# ProjectSIT210.net
KiCad netlist of a schematic drawn in EasyEDA
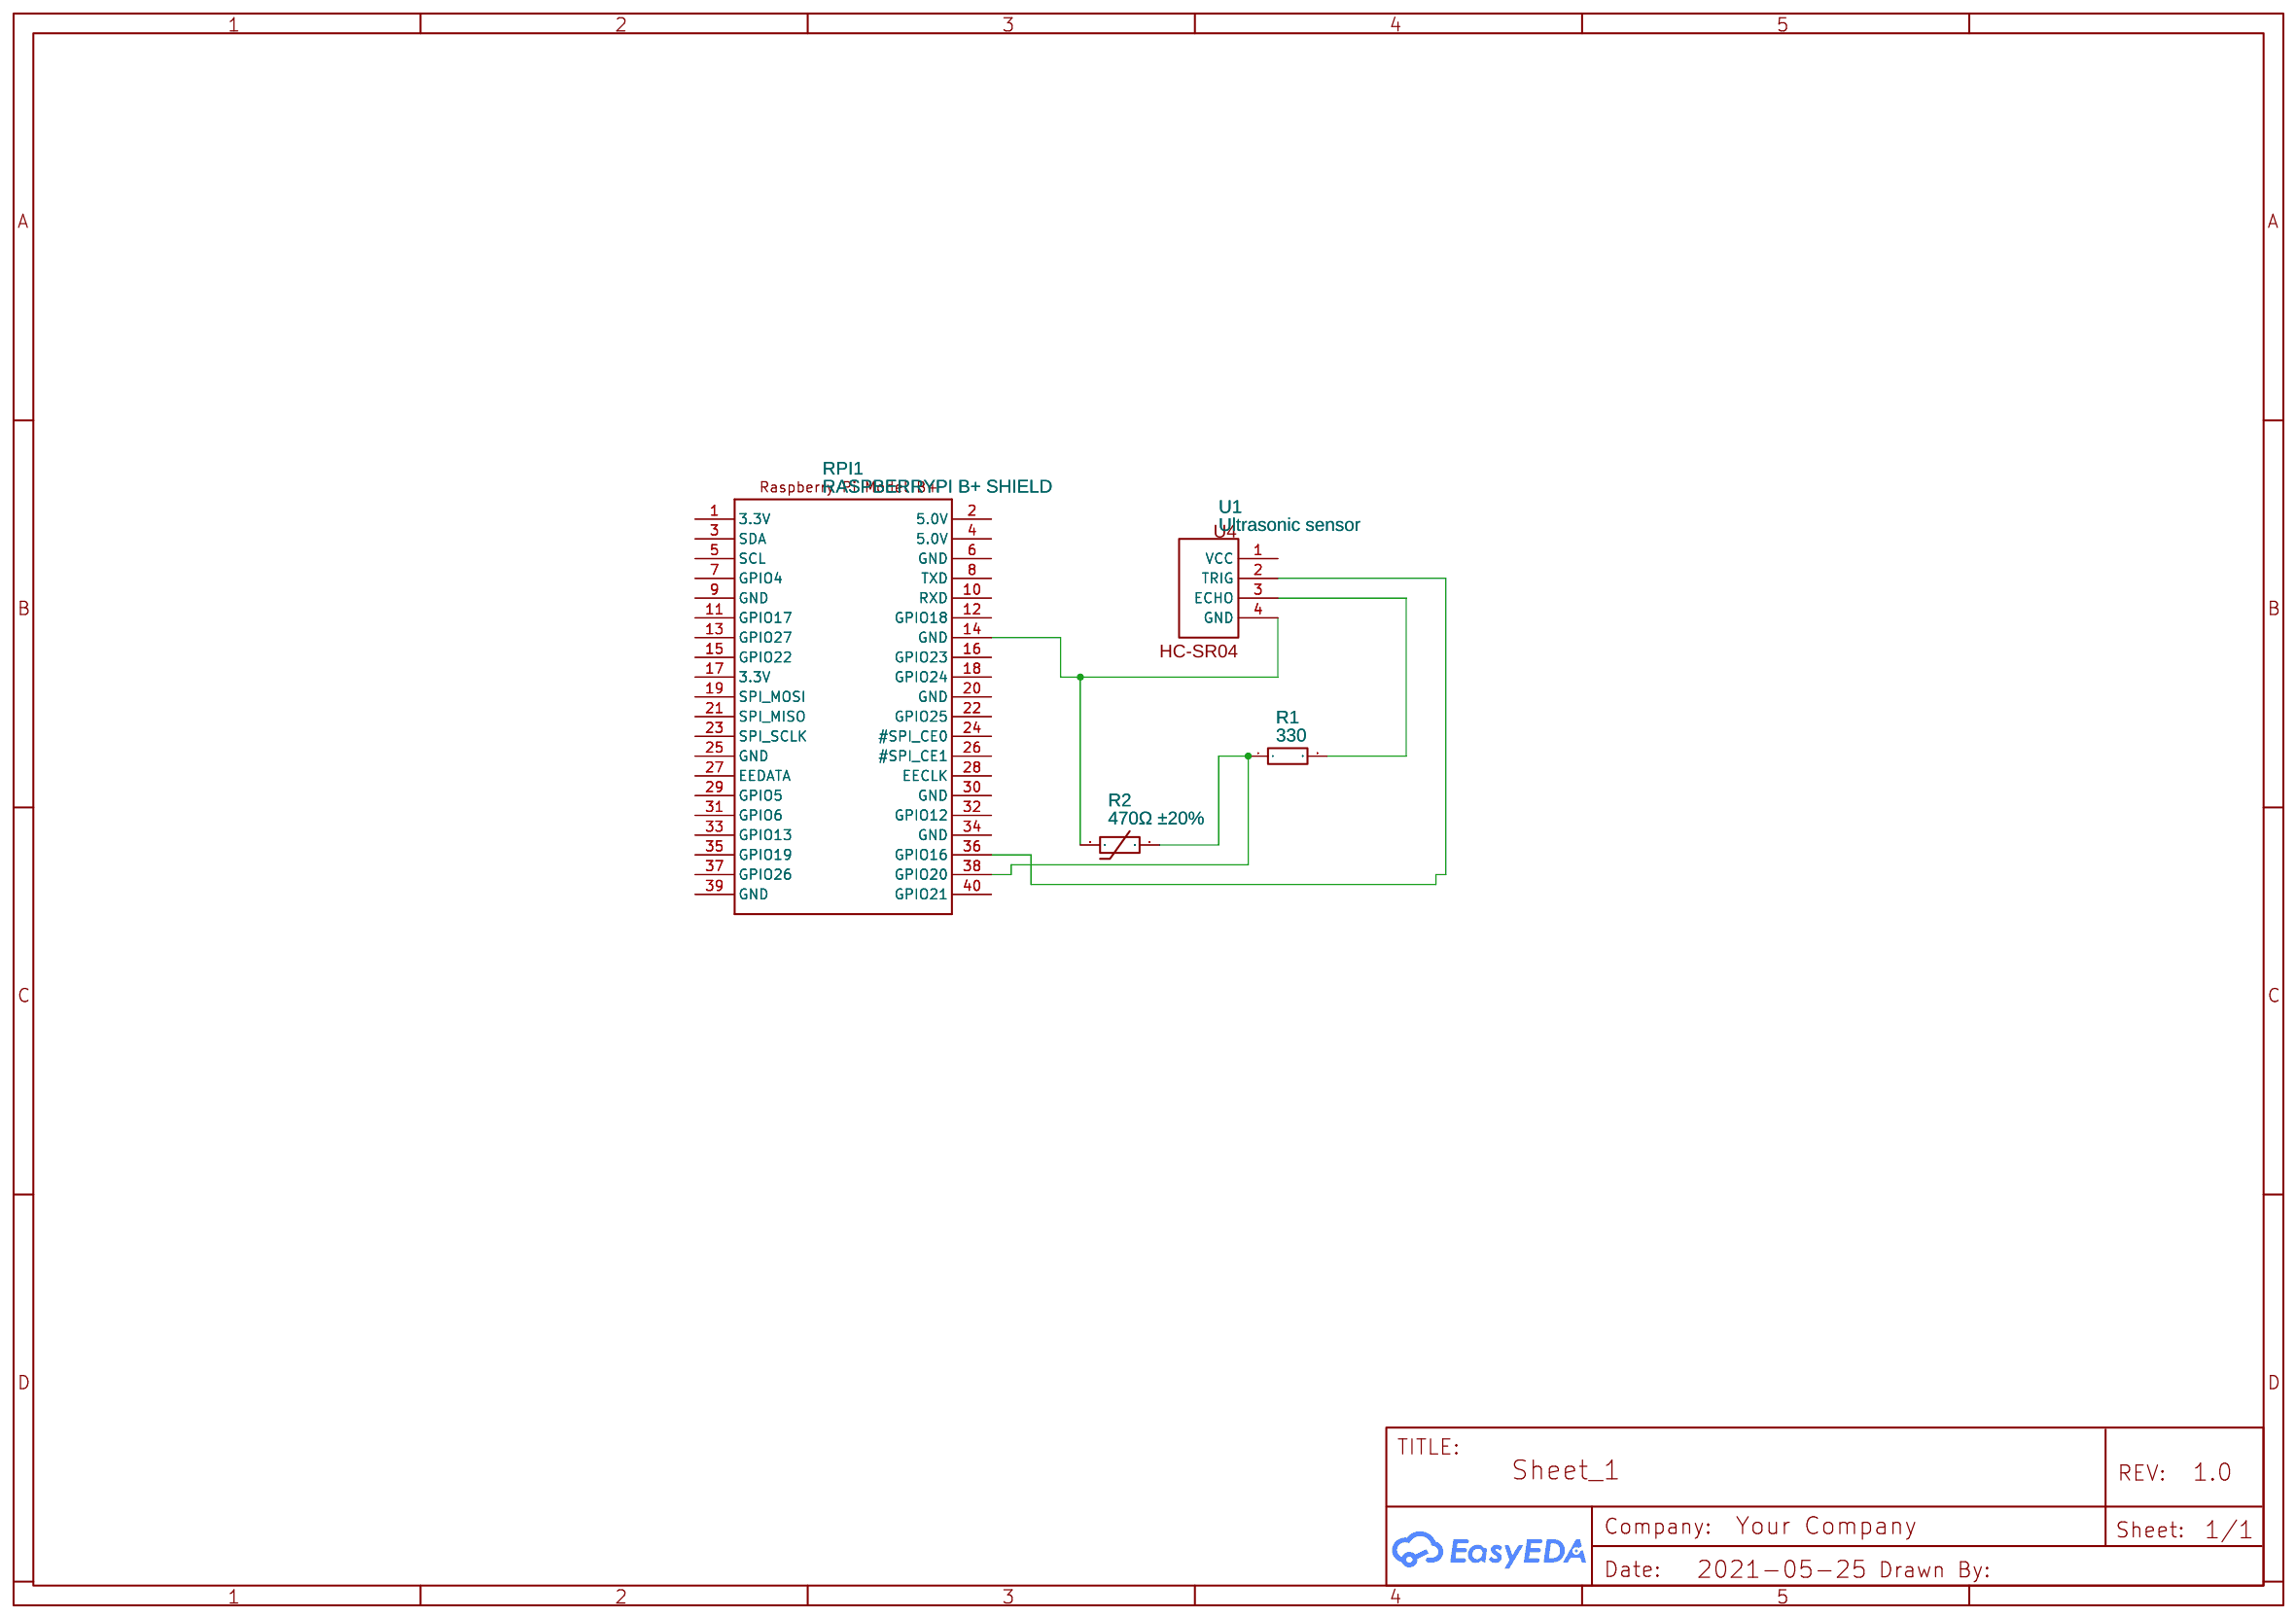
[diagram p0: schematic sheet]

(export (version "E")
  (design (tool "Eeschema 10.0.6"))
  (components
    (comp (ref "R1")
      (value "330")
      (fields (field (name "BOM_Supplier Part") "C10322"))
      (libsource (lib "") (part "330Ω (331) ±5%"))
    )
    (comp (ref "R2")
      (value "470Ω ±20%")
      (fields (field (name "BOM_Manufacturer Part") "MF11 471M") (field (name "BOM_Supplier Part") "C123348"))
      (libsource (lib "") (part "470Ω ±20%"))
    )
    (comp (ref "RPI1") (value "RASPBERRYPI B+ SHIELD") (libsource (lib "") (part "RASPBERRYPI B+ SHIELD")))
    (comp (ref "U1")
      (value "Ultrasonic sensor")
      (fields (field (name "BOM_Manufacturer Part") "ULTRASONIC-HC-SR04"))
      (libsource (lib "") (part "Ultrasonic sensor"))
    )
  )
  (nets
    (net (code "1") (name "Net-(RPI1-GPIO16)") (class "Default")
      (node (ref "RPI1") (pin "36") (pinfunction "GPIO16_36") (pintype "bidirectional"))
      (node (ref "U1") (pin "2") (pinfunction "TRIG_2") (pintype "input"))
    )
    (net (code "2") (name "Net-(RPI1-GPIO20)") (class "Default")
      (node (ref "R1") (pin "1") (pinfunction "1_1") (pintype "unspecified"))
      (node (ref "R2") (pin "2") (pinfunction "2_2") (pintype "unspecified"))
      (node (ref "RPI1") (pin "38") (pinfunction "GPIO20_38") (pintype "bidirectional"))
    )
    (net (code "3") (name "Net-(U1-ECHO)") (class "Default")
      (node (ref "R1") (pin "2") (pinfunction "2_2") (pintype "unspecified"))
      (node (ref "U1") (pin "3") (pinfunction "ECHO_3") (pintype "output"))
    )
    (net (code "4") (name "Net-(U1-GND)") (class "Default")
      (node (ref "R2") (pin "1") (pinfunction "1_1") (pintype "unspecified"))
      (node (ref "RPI1") (pin "14") (pinfunction "GND_14") (pintype "bidirectional"))
      (node (ref "U1") (pin "4") (pinfunction "GND_4") (pintype "passive"))
    )
    (net (code "5") (name "unconnected-(RPI1-#SPI_CE0-Pad24)") (class "Default")
      (node (ref "RPI1") (pin "24") (pinfunction "#SPI_CE0_24") (pintype "bidirectional"))
    )
    (net (code "6") (name "unconnected-(RPI1-#SPI_CE1-Pad26)") (class "Default")
      (node (ref "RPI1") (pin "26") (pinfunction "#SPI_CE1_26") (pintype "bidirectional"))
    )
    (net (code "7") (name "unconnected-(RPI1-3.3V-Pad1)") (class "Default")
      (node (ref "RPI1") (pin "1") (pinfunction "3.3V_1") (pintype "bidirectional"))
    )
    (net (code "8") (name "unconnected-(RPI1-3.3V-Pad17)") (class "Default")
      (node (ref "RPI1") (pin "17") (pinfunction "3.3V_17") (pintype "bidirectional"))
    )
    (net (code "9") (name "unconnected-(RPI1-5.0V-Pad2)") (class "Default")
      (node (ref "RPI1") (pin "2") (pinfunction "5.0V_2") (pintype "bidirectional"))
    )
    (net (code "10") (name "unconnected-(RPI1-5.0V-Pad4)") (class "Default")
      (node (ref "RPI1") (pin "4") (pinfunction "5.0V_4") (pintype "bidirectional"))
    )
    (net (code "11") (name "unconnected-(RPI1-EECLK-Pad28)") (class "Default")
      (node (ref "RPI1") (pin "28") (pinfunction "EECLK_28") (pintype "bidirectional"))
    )
    (net (code "12") (name "unconnected-(RPI1-EEDATA-Pad27)") (class "Default")
      (node (ref "RPI1") (pin "27") (pinfunction "EEDATA_27") (pintype "bidirectional"))
    )
    (net (code "13") (name "unconnected-(RPI1-GND-Pad6)") (class "Default")
      (node (ref "RPI1") (pin "6") (pinfunction "GND_6") (pintype "bidirectional"))
    )
    (net (code "14") (name "unconnected-(RPI1-GND-Pad9)") (class "Default")
      (node (ref "RPI1") (pin "9") (pinfunction "GND_9") (pintype "bidirectional"))
    )
    (net (code "15") (name "unconnected-(RPI1-GND-Pad20)") (class "Default")
      (node (ref "RPI1") (pin "20") (pinfunction "GND_20") (pintype "bidirectional"))
    )
    (net (code "16") (name "unconnected-(RPI1-GND-Pad25)") (class "Default")
      (node (ref "RPI1") (pin "25") (pinfunction "GND_25") (pintype "bidirectional"))
    )
    (net (code "17") (name "unconnected-(RPI1-GND-Pad30)") (class "Default")
      (node (ref "RPI1") (pin "30") (pinfunction "GND_30") (pintype "bidirectional"))
    )
    (net (code "18") (name "unconnected-(RPI1-GND-Pad34)") (class "Default")
      (node (ref "RPI1") (pin "34") (pinfunction "GND_34") (pintype "bidirectional"))
    )
    (net (code "19") (name "unconnected-(RPI1-GND-Pad39)") (class "Default")
      (node (ref "RPI1") (pin "39") (pinfunction "GND_39") (pintype "bidirectional"))
    )
    (net (code "20") (name "unconnected-(RPI1-GPIO4-Pad7)") (class "Default")
      (node (ref "RPI1") (pin "7") (pinfunction "GPIO4_7") (pintype "bidirectional"))
    )
    (net (code "21") (name "unconnected-(RPI1-GPIO5-Pad29)") (class "Default")
      (node (ref "RPI1") (pin "29") (pinfunction "GPIO5_29") (pintype "bidirectional"))
    )
    (net (code "22") (name "unconnected-(RPI1-GPIO6-Pad31)") (class "Default")
      (node (ref "RPI1") (pin "31") (pinfunction "GPIO6_31") (pintype "bidirectional"))
    )
    (net (code "23") (name "unconnected-(RPI1-GPIO12-Pad32)") (class "Default")
      (node (ref "RPI1") (pin "32") (pinfunction "GPIO12_32") (pintype "bidirectional"))
    )
    (net (code "24") (name "unconnected-(RPI1-GPIO13-Pad33)") (class "Default")
      (node (ref "RPI1") (pin "33") (pinfunction "GPIO13_33") (pintype "bidirectional"))
    )
    (net (code "25") (name "unconnected-(RPI1-GPIO17-Pad11)") (class "Default")
      (node (ref "RPI1") (pin "11") (pinfunction "GPIO17_11") (pintype "bidirectional"))
    )
    (net (code "26") (name "unconnected-(RPI1-GPIO18-Pad12)") (class "Default")
      (node (ref "RPI1") (pin "12") (pinfunction "GPIO18_12") (pintype "bidirectional"))
    )
    (net (code "27") (name "unconnected-(RPI1-GPIO19-Pad35)") (class "Default")
      (node (ref "RPI1") (pin "35") (pinfunction "GPIO19_35") (pintype "bidirectional"))
    )
    (net (code "28") (name "unconnected-(RPI1-GPIO21-Pad40)") (class "Default")
      (node (ref "RPI1") (pin "40") (pinfunction "GPIO21_40") (pintype "bidirectional"))
    )
    (net (code "29") (name "unconnected-(RPI1-GPIO22-Pad15)") (class "Default")
      (node (ref "RPI1") (pin "15") (pinfunction "GPIO22_15") (pintype "bidirectional"))
    )
    (net (code "30") (name "unconnected-(RPI1-GPIO23-Pad16)") (class "Default")
      (node (ref "RPI1") (pin "16") (pinfunction "GPIO23_16") (pintype "bidirectional"))
    )
    (net (code "31") (name "unconnected-(RPI1-GPIO24-Pad18)") (class "Default")
      (node (ref "RPI1") (pin "18") (pinfunction "GPIO24_18") (pintype "bidirectional"))
    )
    (net (code "32") (name "unconnected-(RPI1-GPIO25-Pad22)") (class "Default")
      (node (ref "RPI1") (pin "22") (pinfunction "GPIO25_22") (pintype "bidirectional"))
    )
    (net (code "33") (name "unconnected-(RPI1-GPIO26-Pad37)") (class "Default")
      (node (ref "RPI1") (pin "37") (pinfunction "GPIO26_37") (pintype "bidirectional"))
    )
    (net (code "34") (name "unconnected-(RPI1-GPIO27-Pad13)") (class "Default")
      (node (ref "RPI1") (pin "13") (pinfunction "GPIO27_13") (pintype "bidirectional"))
    )
    (net (code "35") (name "unconnected-(RPI1-RXD-Pad10)") (class "Default")
      (node (ref "RPI1") (pin "10") (pinfunction "RXD_10") (pintype "bidirectional"))
    )
    (net (code "36") (name "unconnected-(RPI1-SCL-Pad5)") (class "Default")
      (node (ref "RPI1") (pin "5") (pinfunction "SCL_5") (pintype "bidirectional"))
    )
    (net (code "37") (name "unconnected-(RPI1-SDA-Pad3)") (class "Default")
      (node (ref "RPI1") (pin "3") (pinfunction "SDA_3") (pintype "bidirectional"))
    )
    (net (code "38") (name "unconnected-(RPI1-SPI_MISO-Pad21)") (class "Default")
      (node (ref "RPI1") (pin "21") (pinfunction "SPI_MISO_21") (pintype "bidirectional"))
    )
    (net (code "39") (name "unconnected-(RPI1-SPI_MOSI-Pad19)") (class "Default")
      (node (ref "RPI1") (pin "19") (pinfunction "SPI_MOSI_19") (pintype "bidirectional"))
    )
    (net (code "40") (name "unconnected-(RPI1-SPI_SCLK-Pad23)") (class "Default")
      (node (ref "RPI1") (pin "23") (pinfunction "SPI_SCLK_23") (pintype "bidirectional"))
    )
    (net (code "41") (name "unconnected-(RPI1-TXD-Pad8)") (class "Default")
      (node (ref "RPI1") (pin "8") (pinfunction "TXD_8") (pintype "bidirectional"))
    )
    (net (code "42") (name "unconnected-(U1-VCC-Pad1)") (class "Default")
      (node (ref "U1") (pin "1") (pinfunction "VCC_1") (pintype "passive"))
    )
  )
)
